# schematic.net
KiCad netlist of a schematic drawn in Altium Designer
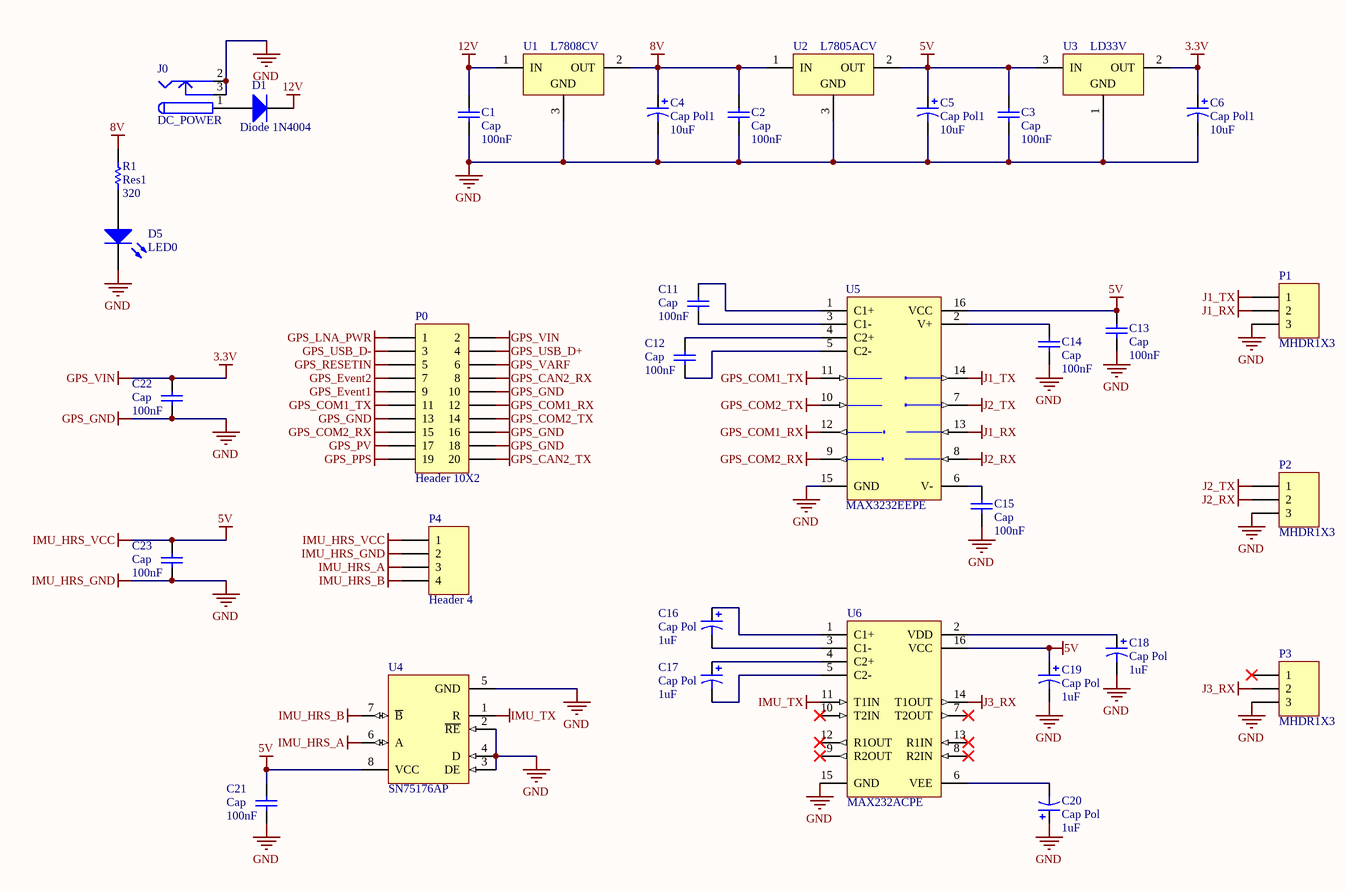
[diagram p0: schematic.SchDoc]

(export (version "E")
  (design (tool "Eeschema 10.0.6"))
  (components
    (comp (ref "C1")
      (value "Cap")
      (footprint "VP32-3.2")
      (description "Capacitor")
      (fields (field (name "ALTIUM_VALUE") "100nF") (field (name "PUBLISHER") "Altium Limited"))
      (libsource (lib "Miscellaneous Devices") (part "Cap"))
    )
    (comp (ref "C2")
      (value "Cap")
      (footprint "VP32-3.2")
      (description "Capacitor")
      (fields (field (name "ALTIUM_VALUE") "100nF") (field (name "PUBLISHER") "Altium Limited"))
      (libsource (lib "Miscellaneous Devices") (part "Cap"))
    )
    (comp (ref "C3")
      (value "Cap")
      (footprint "VP32-3.2")
      (description "Capacitor")
      (fields (field (name "ALTIUM_VALUE") "100nF") (field (name "PUBLISHER") "Altium Limited"))
      (libsource (lib "Miscellaneous Devices") (part "Cap"))
    )
    (comp (ref "C4")
      (value "Cap Pol1")
      (footprint "B")
      (description "Polarized Capacitor (Radial)")
      (fields (field (name "ALTIUM_VALUE") "10uF") (field (name "PUBLISHER") "Altium Limited"))
      (libsource (lib "Miscellaneous Devices") (part "Cap Pol1"))
    )
    (comp (ref "C5")
      (value "Cap Pol1")
      (footprint "B")
      (description "Polarized Capacitor (Radial)")
      (fields (field (name "ALTIUM_VALUE") "10uF") (field (name "PUBLISHER") "Altium Limited"))
      (libsource (lib "Miscellaneous Devices") (part "Cap Pol1"))
    )
    (comp (ref "C6")
      (value "Cap Pol1")
      (footprint "B")
      (description "Polarized Capacitor (Radial)")
      (fields (field (name "ALTIUM_VALUE") "10uF") (field (name "PUBLISHER") "Altium Limited"))
      (libsource (lib "Miscellaneous Devices") (part "Cap Pol1"))
    )
    (comp (ref "C11")
      (value "Cap")
      (footprint "VP32-3.2")
      (description "Capacitor")
      (fields (field (name "ALTIUM_VALUE") "100nF") (field (name "PUBLISHER") "Altium Limited"))
      (libsource (lib "Miscellaneous Devices") (part "Cap"))
    )
    (comp (ref "C12")
      (value "Cap")
      (footprint "VP32-3.2")
      (description "Capacitor")
      (fields (field (name "ALTIUM_VALUE") "100nF") (field (name "PUBLISHER") "Altium Limited"))
      (libsource (lib "Miscellaneous Devices") (part "Cap"))
    )
    (comp (ref "C13")
      (value "Cap")
      (footprint "VP32-3.2")
      (description "Capacitor")
      (fields (field (name "ALTIUM_VALUE") "100nF") (field (name "PUBLISHER") "Altium Limited"))
      (libsource (lib "Miscellaneous Devices") (part "Cap"))
    )
    (comp (ref "C14")
      (value "Cap")
      (footprint "VP32-3.2")
      (description "Capacitor")
      (fields (field (name "ALTIUM_VALUE") "100nF") (field (name "PUBLISHER") "Altium Limited"))
      (libsource (lib "Miscellaneous Devices") (part "Cap"))
    )
    (comp (ref "C15")
      (value "Cap")
      (footprint "VP32-3.2")
      (description "Capacitor")
      (fields (field (name "ALTIUM_VALUE") "100nF") (field (name "PUBLISHER") "Altium Limited"))
      (libsource (lib "Miscellaneous Devices") (part "Cap"))
    )
    (comp (ref "C16")
      (value "Cap Pol")
      (footprint "B")
      (description "Polarized Capacitor (Radial)")
      (fields (field (name "ALTIUM_VALUE") "1uF") (field (name "PUBLISHER") "Altium Limited"))
      (libsource (lib "Miscellaneous Devices") (part "Cap Pol1"))
    )
    (comp (ref "C17")
      (value "Cap Pol")
      (footprint "B")
      (description "Polarized Capacitor (Radial)")
      (fields (field (name "ALTIUM_VALUE") "1uF") (field (name "PUBLISHER") "Altium Limited"))
      (libsource (lib "Miscellaneous Devices") (part "Cap Pol1"))
    )
    (comp (ref "C18")
      (value "Cap Pol")
      (footprint "B")
      (description "Polarized Capacitor (Radial)")
      (fields (field (name "ALTIUM_VALUE") "1uF") (field (name "PUBLISHER") "Altium Limited"))
      (libsource (lib "Miscellaneous Devices") (part "Cap Pol1"))
    )
    (comp (ref "C19")
      (value "Cap Pol")
      (footprint "B")
      (description "Polarized Capacitor (Radial)")
      (fields (field (name "ALTIUM_VALUE") "1uF") (field (name "PUBLISHER") "Altium Limited"))
      (libsource (lib "Miscellaneous Devices") (part "Cap Pol1"))
    )
    (comp (ref "C20")
      (value "Cap Pol")
      (footprint "B")
      (description "Polarized Capacitor (Radial)")
      (fields (field (name "ALTIUM_VALUE") "1uF") (field (name "PUBLISHER") "Altium Limited"))
      (libsource (lib "Miscellaneous Devices") (part "Cap Pol1"))
    )
    (comp (ref "C21")
      (value "Cap")
      (footprint "VP32-3.2")
      (description "Capacitor")
      (fields (field (name "ALTIUM_VALUE") "100nF") (field (name "PUBLISHER") "Altium Limited"))
      (libsource (lib "Miscellaneous Devices") (part "Cap"))
    )
    (comp (ref "C22")
      (value "Cap")
      (footprint "VP32-3.2")
      (description "Capacitor")
      (fields (field (name "ALTIUM_VALUE") "100nF") (field (name "PUBLISHER") "Altium Limited"))
      (libsource (lib "Miscellaneous Devices") (part "Cap"))
    )
    (comp (ref "C23")
      (value "Cap")
      (footprint "VP32-3.2")
      (description "Capacitor")
      (fields (field (name "ALTIUM_VALUE") "100nF") (field (name "PUBLISHER") "Altium Limited"))
      (libsource (lib "Miscellaneous Devices") (part "Cap"))
    )
    (comp (ref "D1")
      (value "Diode 1N4004")
      (footprint "DO-41")
      (description "1 Amp General Purpose Rectifier")
      (fields (field (name "PUBLISHER") "Altium Limited"))
      (libsource (lib "Miscellaneous Devices") (part "Diode 1N4004"))
    )
    (comp (ref "D5")
      (value "LED0")
      (footprint "B")
      (description "Typical INFRARED GaAs LED")
      (fields (field (name "PUBLISHER") "Altium Limited"))
      (libsource (lib "Miscellaneous Devices") (part "LED0"))
    )
    (comp (ref "J0")
      (value "DC_POWER")
      (footprint "DC_POWER")
      (description "Low Voltage Power Supply Connector")
      (fields (field (name "PUBLISHER") "Altium Limited"))
      (libsource (lib "schlib") (part "DC_POWER"))
    )
    (comp (ref "P0")
      (value "Header 10X2")
      (footprint "HDR2X10")
      (description "Header, 10-Pin, Dual row")
      (fields (field (name "PUBLISHER") "Altium Limited"))
      (libsource (lib "Miscellaneous Connectors") (part "Header 10X2"))
    )
    (comp (ref "P1")
      (value "MHDR1X3")
      (footprint "HDR1X3")
      (description "Header, 3-Pin")
      (fields (field (name "PUBLISHER") "Altium Limited"))
      (libsource (lib "Miscellaneous Connectors") (part "MHDR1X3"))
    )
    (comp (ref "P2")
      (value "MHDR1X3")
      (footprint "HDR1X3")
      (description "Header, 3-Pin")
      (fields (field (name "PUBLISHER") "Altium Limited"))
      (libsource (lib "Miscellaneous Connectors") (part "MHDR1X3"))
    )
    (comp (ref "P3")
      (value "MHDR1X3")
      (footprint "HDR1X3")
      (description "Header, 3-Pin")
      (fields (field (name "PUBLISHER") "Altium Limited"))
      (libsource (lib "Miscellaneous Connectors") (part "MHDR1X3"))
    )
    (comp (ref "P4")
      (value "Header 4")
      (footprint "HDR1X4")
      (description "Header, 4-Pin")
      (fields (field (name "PUBLISHER") "Altium Limited"))
      (libsource (lib "Miscellaneous Connectors") (part "Header 4"))
    )
    (comp (ref "R1")
      (value "Res1")
      (footprint "AXIAL-0.3")
      (description "Resistor")
      (fields (field (name "ALTIUM_VALUE") "320") (field (name "PUBLISHER") "Altium Limited"))
      (libsource (lib "Miscellaneous Devices") (part "Res1"))
    )
    (comp (ref "U1")
      (value "L7808CV")
      (footprint "TO220ABN")
      (description "Positive Voltage Regulator")
      (fields (field (name "PUBLISHER") "Altium Limited"))
      (libsource (lib "ST Power Mgt Voltage Regulator") (part "L7808CV"))
    )
    (comp (ref "U2")
      (value "L7805ACV")
      (footprint "TO220ABN")
      (description "Precision 1A Regulator")
      (fields (field (name "PUBLISHER") "Altium Limited"))
      (libsource (lib "ST Power Mgt Voltage Regulator") (part "L7805ACV"))
    )
    (comp (ref "U3")
      (value "LD33V")
      (footprint "T03B")
      (description "800mA Low-Dropout Linear Regulator")
      (fields
        (field (name "PARTNUMBER") "LM1117T-3.3")
        (field (name "MANUFACTURER") "National Semiconductor")
        (field (name "PUBLISHER") "Altium Limited")
      )
      (libsource (lib "NSC LDO") (part "LM1117T-3.3"))
    )
    (comp (ref "U4")
      (value "SN75176AP")
      (footprint "P008")
      (description "Differential Bus Transceiver")
      (fields (field (name "PUBLISHER") "Altium Limited"))
      (libsource (lib "TI Interface Line Transceiver") (part "SN75176AP"))
    )
    (comp (ref "U5")
      (value "MAX3232EEPE")
      (footprint "Maxim Footprints:PE16")
      (description "±15kV ESD-Protected, 3.0V to 5.5V, Low-Power, up to 250kbps, True RS-232 Transceiver")
      (fields (field (name "PUBLISHER") "Altium Limited"))
      (libsource (lib "Maxim Communication Transceiver") (part "MAX3232EEPE"))
    )
    (comp (ref "U6")
      (value "MAX232ACPE")
      (footprint "PE16A")
      (description "+5V Powered, Multi-Channel RS-232 Driver/Receiver")
      (fields (field (name "PUBLISHER") "Altium Limited"))
      (libsource (lib "Maxim Communication Transceiver") (part "MAX232ACPE"))
    )
  )
  (nets
    (net (code "1") (name "3.3V") (class "Default")
      (node (ref "C22") (pin "2") (pinfunction "2_2") (pintype "passive"))
      (node (ref "C6") (pin "1") (pinfunction "1_1") (pintype "passive"))
      (node (ref "P0") (pin "2") (pinfunction "2_2") (pintype "passive"))
      (node (ref "U3") (pin "2") (pinfunction "OUT_2") (pintype "power_in"))
    )
    (net (code "2") (name "5V") (class "Default")
      (node (ref "C13") (pin "2") (pinfunction "2_2") (pintype "passive"))
      (node (ref "C19") (pin "1") (pinfunction "1_1") (pintype "passive"))
      (node (ref "C21") (pin "2") (pinfunction "2_2") (pintype "passive"))
      (node (ref "C23") (pin "2") (pinfunction "2_2") (pintype "passive"))
      (node (ref "C3") (pin "1") (pinfunction "1_1") (pintype "passive"))
      (node (ref "C5") (pin "1") (pinfunction "1_1") (pintype "passive"))
      (node (ref "P4") (pin "1") (pinfunction "1_1") (pintype "passive"))
      (node (ref "U2") (pin "2") (pinfunction "OUT_2") (pintype "power_in"))
      (node (ref "U3") (pin "3") (pinfunction "IN_3") (pintype "power_in"))
      (node (ref "U4") (pin "8") (pinfunction "VCC_8") (pintype "power_in"))
      (node (ref "U5") (pin "16") (pinfunction "VCC_16") (pintype "power_in"))
      (node (ref "U6") (pin "16") (pinfunction "VCC_16") (pintype "power_in"))
    )
    (net (code "3") (name "8V") (class "Default")
      (node (ref "C2") (pin "1") (pinfunction "1_1") (pintype "passive"))
      (node (ref "C4") (pin "1") (pinfunction "1_1") (pintype "passive"))
      (node (ref "R1") (pin "2") (pinfunction "2_2") (pintype "passive"))
      (node (ref "U1") (pin "2") (pinfunction "OUT_2") (pintype "power_in"))
      (node (ref "U2") (pin "1") (pinfunction "IN_1") (pintype "power_in"))
    )
    (net (code "4") (name "12V") (class "Default")
      (node (ref "C1") (pin "1") (pinfunction "1_1") (pintype "passive"))
      (node (ref "D1") (pin "2") (pinfunction "K_2") (pintype "passive"))
      (node (ref "U1") (pin "1") (pinfunction "IN_1") (pintype "power_in"))
    )
    (net (code "5") (name "GND") (class "Default")
      (node (ref "C1") (pin "2") (pinfunction "2_2") (pintype "passive"))
      (node (ref "C13") (pin "1") (pinfunction "1_1") (pintype "passive"))
      (node (ref "C14") (pin "1") (pinfunction "1_1") (pintype "passive"))
      (node (ref "C15") (pin "1") (pinfunction "1_1") (pintype "passive"))
      (node (ref "C18") (pin "2") (pinfunction "2_2") (pintype "passive"))
      (node (ref "C19") (pin "2") (pinfunction "2_2") (pintype "passive"))
      (node (ref "C2") (pin "2") (pinfunction "2_2") (pintype "passive"))
      (node (ref "C20") (pin "1") (pinfunction "1_1") (pintype "passive"))
      (node (ref "C21") (pin "1") (pinfunction "1_1") (pintype "passive"))
      (node (ref "C22") (pin "1") (pinfunction "1_1") (pintype "passive"))
      (node (ref "C23") (pin "1") (pinfunction "1_1") (pintype "passive"))
      (node (ref "C3") (pin "2") (pinfunction "2_2") (pintype "passive"))
      (node (ref "C4") (pin "2") (pinfunction "2_2") (pintype "passive"))
      (node (ref "C5") (pin "2") (pinfunction "2_2") (pintype "passive"))
      (node (ref "C6") (pin "2") (pinfunction "2_2") (pintype "passive"))
      (node (ref "D5") (pin "2") (pinfunction "K_2") (pintype "passive"))
      (node (ref "J0") (pin "2") (pinfunction "2_2") (pintype "power_in"))
      (node (ref "J0") (pin "3") (pinfunction "3_3") (pintype "power_in"))
      (node (ref "P0") (pin "10") (pinfunction "10_10") (pintype "passive"))
      (node (ref "P0") (pin "13") (pinfunction "13_13") (pintype "passive"))
      (node (ref "P0") (pin "16") (pinfunction "16_16") (pintype "passive"))
      (node (ref "P0") (pin "18") (pinfunction "18_18") (pintype "passive"))
      (node (ref "P1") (pin "3") (pinfunction "3_3") (pintype "passive"))
      (node (ref "P2") (pin "3") (pinfunction "3_3") (pintype "passive"))
      (node (ref "P3") (pin "3") (pinfunction "3_3") (pintype "passive"))
      (node (ref "P4") (pin "2") (pinfunction "2_2") (pintype "passive"))
      (node (ref "U1") (pin "3") (pinfunction "GND_3") (pintype "power_in"))
      (node (ref "U2") (pin "3") (pinfunction "GND_3") (pintype "power_in"))
      (node (ref "U3") (pin "1") (pinfunction "GND_1") (pintype "power_in"))
      (node (ref "U4") (pin "2") (pinfunction "~{RE}_2") (pintype "input"))
      (node (ref "U4") (pin "3") (pinfunction "DE_3") (pintype "input"))
      (node (ref "U4") (pin "4") (pinfunction "D_4") (pintype "input"))
      (node (ref "U4") (pin "5") (pinfunction "GND_5") (pintype "power_in"))
      (node (ref "U5") (pin "15") (pinfunction "GND_15") (pintype "power_in"))
      (node (ref "U6") (pin "15") (pinfunction "GND_15") (pintype "power_in"))
    )
    (net (code "6") (name "GPS_CAN2_RX") (class "Default")
      (node (ref "P0") (pin "8") (pinfunction "8_8") (pintype "passive"))
    )
    (net (code "7") (name "GPS_CAN2_TX") (class "Default")
      (node (ref "P0") (pin "20") (pinfunction "20_20") (pintype "passive"))
    )
    (net (code "8") (name "GPS_COM1_RX") (class "Default")
      (node (ref "P0") (pin "12") (pinfunction "12_12") (pintype "passive"))
      (node (ref "U5") (pin "12") (pinfunction "R1OUT_12") (pintype "output"))
    )
    (net (code "9") (name "GPS_COM1_TX") (class "Default")
      (node (ref "P0") (pin "11") (pinfunction "11_11") (pintype "passive"))
      (node (ref "U5") (pin "11") (pinfunction "T1IN_11") (pintype "input"))
    )
    (net (code "10") (name "GPS_COM2_RX") (class "Default")
      (node (ref "P0") (pin "15") (pinfunction "15_15") (pintype "passive"))
      (node (ref "U5") (pin "9") (pinfunction "R2OUT_9") (pintype "output"))
    )
    (net (code "11") (name "GPS_COM2_TX") (class "Default")
      (node (ref "P0") (pin "14") (pinfunction "14_14") (pintype "passive"))
      (node (ref "U5") (pin "10") (pinfunction "T2IN_10") (pintype "input"))
    )
    (net (code "12") (name "GPS_Event1") (class "Default")
      (node (ref "P0") (pin "9") (pinfunction "9_9") (pintype "passive"))
    )
    (net (code "13") (name "GPS_Event2") (class "Default")
      (node (ref "P0") (pin "7") (pinfunction "7_7") (pintype "passive"))
    )
    (net (code "14") (name "GPS_LNA_PWR") (class "Default")
      (node (ref "P0") (pin "1") (pinfunction "1_1") (pintype "passive"))
    )
    (net (code "15") (name "GPS_PPS") (class "Default")
      (node (ref "P0") (pin "19") (pinfunction "19_19") (pintype "passive"))
    )
    (net (code "16") (name "GPS_PV") (class "Default")
      (node (ref "P0") (pin "17") (pinfunction "17_17") (pintype "passive"))
    )
    (net (code "17") (name "GPS_RESETIN") (class "Default")
      (node (ref "P0") (pin "5") (pinfunction "5_5") (pintype "passive"))
    )
    (net (code "18") (name "GPS_USB_D+") (class "Default")
      (node (ref "P0") (pin "4") (pinfunction "4_4") (pintype "passive"))
    )
    (net (code "19") (name "GPS_USB_D-") (class "Default")
      (node (ref "P0") (pin "3") (pinfunction "3_3") (pintype "passive"))
    )
    (net (code "20") (name "GPS_VARF") (class "Default")
      (node (ref "P0") (pin "6") (pinfunction "6_6") (pintype "passive"))
    )
    (net (code "21") (name "IMU_HRS_A") (class "Default")
      (node (ref "P4") (pin "3") (pinfunction "3_3") (pintype "passive"))
      (node (ref "U4") (pin "6") (pinfunction "A_6") (pintype "bidirectional"))
    )
    (net (code "22") (name "IMU_HRS_B") (class "Default")
      (node (ref "P4") (pin "4") (pinfunction "4_4") (pintype "passive"))
      (node (ref "U4") (pin "7") (pinfunction "~{B}_7") (pintype "bidirectional"))
    )
    (net (code "23") (name "IMU_TX") (class "Default")
      (node (ref "U4") (pin "1") (pinfunction "R_1") (pintype "tri_state"))
      (node (ref "U6") (pin "11") (pinfunction "T1IN_11") (pintype "input"))
    )
    (net (code "24") (name "J1_RX") (class "Default")
      (node (ref "P1") (pin "2") (pinfunction "2_2") (pintype "passive"))
      (node (ref "U5") (pin "13") (pinfunction "R1IN_13") (pintype "input"))
    )
    (net (code "25") (name "J1_TX") (class "Default")
      (node (ref "P1") (pin "1") (pinfunction "1_1") (pintype "passive"))
      (node (ref "U5") (pin "14") (pinfunction "T1OUT_14") (pintype "output"))
    )
    (net (code "26") (name "J2_RX") (class "Default")
      (node (ref "P2") (pin "2") (pinfunction "2_2") (pintype "passive"))
      (node (ref "U5") (pin "8") (pinfunction "R2IN_8") (pintype "input"))
    )
    (net (code "27") (name "J2_TX") (class "Default")
      (node (ref "P2") (pin "1") (pinfunction "1_1") (pintype "passive"))
      (node (ref "U5") (pin "7") (pinfunction "T2OUT_7") (pintype "output"))
    )
    (net (code "28") (name "J3_RX") (class "Default")
      (node (ref "P3") (pin "2") (pinfunction "2_2") (pintype "passive"))
      (node (ref "U6") (pin "14") (pinfunction "T1OUT_14") (pintype "output"))
    )
    (net (code "29") (name "Net-(D1-A)") (class "Default")
      (node (ref "D1") (pin "1") (pinfunction "A_1") (pintype "passive"))
      (node (ref "J0") (pin "1") (pinfunction "1_1") (pintype "power_in"))
    )
    (net (code "30") (name "Net-(D5-A)") (class "Default")
      (node (ref "D5") (pin "1") (pinfunction "A_1") (pintype "passive"))
      (node (ref "R1") (pin "1") (pinfunction "1_1") (pintype "passive"))
    )
    (net (code "31") (name "Net-(U5-C1+)") (class "Default")
      (node (ref "C11") (pin "2") (pinfunction "2_2") (pintype "passive"))
      (node (ref "U5") (pin "1") (pinfunction "C1+_1") (pintype "passive"))
    )
    (net (code "32") (name "Net-(U5-C1-)") (class "Default")
      (node (ref "C11") (pin "1") (pinfunction "1_1") (pintype "passive"))
      (node (ref "U5") (pin "3") (pinfunction "C1-_3") (pintype "passive"))
    )
    (net (code "33") (name "Net-(U5-C2+)") (class "Default")
      (node (ref "C12") (pin "2") (pinfunction "2_2") (pintype "passive"))
      (node (ref "U5") (pin "4") (pinfunction "C2+_4") (pintype "passive"))
    )
    (net (code "34") (name "Net-(U5-C2-)") (class "Default")
      (node (ref "C12") (pin "1") (pinfunction "1_1") (pintype "passive"))
      (node (ref "U5") (pin "5") (pinfunction "C2-_5") (pintype "passive"))
    )
    (net (code "35") (name "Net-(U5-V+)") (class "Default")
      (node (ref "C14") (pin "2") (pinfunction "2_2") (pintype "passive"))
      (node (ref "U5") (pin "2") (pinfunction "V+_2") (pintype "power_in"))
    )
    (net (code "36") (name "Net-(U5-V-)") (class "Default")
      (node (ref "C15") (pin "2") (pinfunction "2_2") (pintype "passive"))
      (node (ref "U5") (pin "6") (pinfunction "V-_6") (pintype "power_in"))
    )
    (net (code "37") (name "Net-(U6-C1+)") (class "Default")
      (node (ref "C16") (pin "1") (pinfunction "1_1") (pintype "passive"))
      (node (ref "U6") (pin "1") (pinfunction "C1+_1") (pintype "passive"))
    )
    (net (code "38") (name "Net-(U6-C1-)") (class "Default")
      (node (ref "C16") (pin "2") (pinfunction "2_2") (pintype "passive"))
      (node (ref "U6") (pin "3") (pinfunction "C1-_3") (pintype "passive"))
    )
    (net (code "39") (name "Net-(U6-C2+)") (class "Default")
      (node (ref "C17") (pin "1") (pinfunction "1_1") (pintype "passive"))
      (node (ref "U6") (pin "4") (pinfunction "C2+_4") (pintype "passive"))
    )
    (net (code "40") (name "Net-(U6-C2-)") (class "Default")
      (node (ref "C17") (pin "2") (pinfunction "2_2") (pintype "passive"))
      (node (ref "U6") (pin "5") (pinfunction "C2-_5") (pintype "passive"))
    )
    (net (code "41") (name "Net-(U6-VDD)") (class "Default")
      (node (ref "C18") (pin "1") (pinfunction "1_1") (pintype "passive"))
      (node (ref "U6") (pin "2") (pinfunction "VDD_2") (pintype "power_in"))
    )
    (net (code "42") (name "Net-(U6-VEE)") (class "Default")
      (node (ref "C20") (pin "2") (pinfunction "2_2") (pintype "passive"))
      (node (ref "U6") (pin "6") (pinfunction "VEE_6") (pintype "power_in"))
    )
    (net (code "43") (name "unconnected-(P3-Pad1)") (class "Default")
      (node (ref "P3") (pin "1") (pinfunction "1_1") (pintype "passive+no_connect"))
    )
    (net (code "44") (name "unconnected-(U6-R1IN-Pad13)") (class "Default")
      (node (ref "U6") (pin "13") (pinfunction "R1IN_13") (pintype "input+no_connect"))
    )
    (net (code "45") (name "unconnected-(U6-R1OUT-Pad12)") (class "Default")
      (node (ref "U6") (pin "12") (pinfunction "R1OUT_12") (pintype "output+no_connect"))
    )
    (net (code "46") (name "unconnected-(U6-R2IN-Pad8)") (class "Default")
      (node (ref "U6") (pin "8") (pinfunction "R2IN_8") (pintype "input+no_connect"))
    )
    (net (code "47") (name "unconnected-(U6-R2OUT-Pad9)") (class "Default")
      (node (ref "U6") (pin "9") (pinfunction "R2OUT_9") (pintype "output+no_connect"))
    )
    (net (code "48") (name "unconnected-(U6-T2IN-Pad10)") (class "Default")
      (node (ref "U6") (pin "10") (pinfunction "T2IN_10") (pintype "input+no_connect"))
    )
    (net (code "49") (name "unconnected-(U6-T2OUT-Pad7)") (class "Default")
      (node (ref "U6") (pin "7") (pinfunction "T2OUT_7") (pintype "output+no_connect"))
    )
  )
)
